# LatencyTester.net
KiCad netlist of a schematic drawn in EAGLE
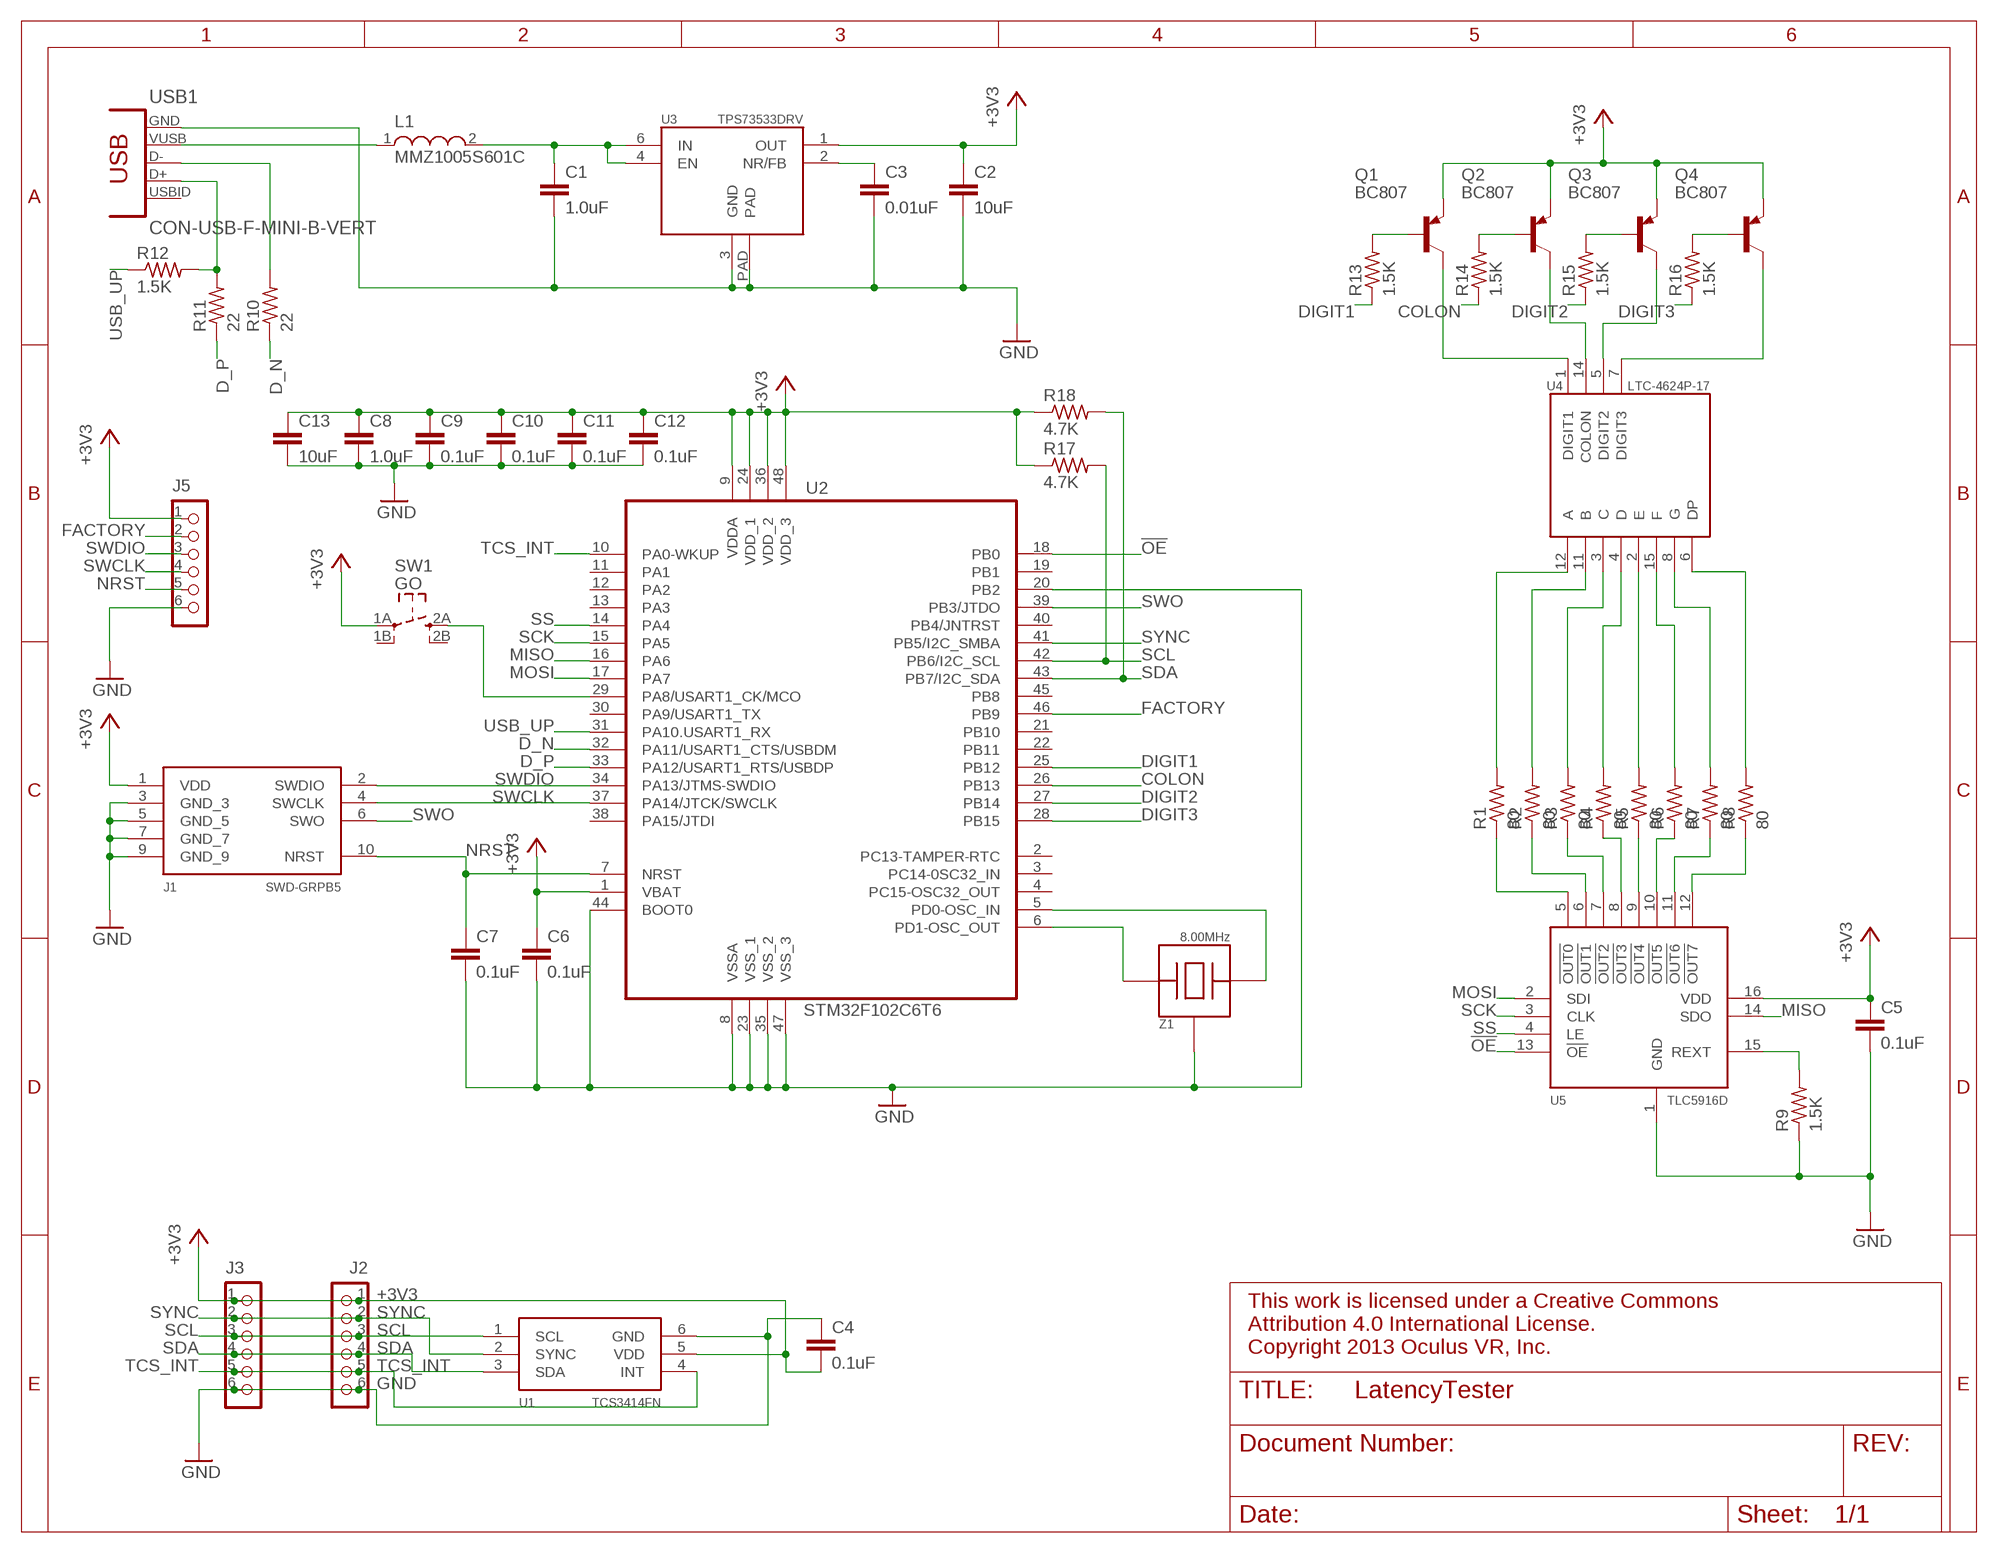
[diagram p0: schematic, sheet 1]

(export (version "E")
  (design (tool "Eeschema 10.0.6"))
  (components
    (comp (ref "C1")
      (value "1.0uF")
      (footprint "eagle-import:C0402")
      (libsource (lib "eagle-import") (part "C-EUC0402"))
    )
    (comp (ref "C2")
      (value "10uF")
      (footprint "eagle-import:C0805")
      (libsource (lib "eagle-import") (part "C-EUC0805"))
    )
    (comp (ref "C3")
      (value "0.01uF")
      (footprint "eagle-import:C0402")
      (libsource (lib "eagle-import") (part "C-EUC0402"))
    )
    (comp (ref "C4")
      (value "0.1uF")
      (footprint "eagle-import:C0402")
      (libsource (lib "eagle-import") (part "C-EUC0402"))
    )
    (comp (ref "C5")
      (value "0.1uF")
      (footprint "eagle-import:C0402")
      (libsource (lib "eagle-import") (part "C-EUC0402"))
    )
    (comp (ref "C6")
      (value "0.1uF")
      (footprint "eagle-import:C0402")
      (libsource (lib "eagle-import") (part "C-EUC0402"))
    )
    (comp (ref "C7")
      (value "0.1uF")
      (footprint "eagle-import:C0402")
      (libsource (lib "eagle-import") (part "C-EUC0402"))
    )
    (comp (ref "C8")
      (value "1.0uF")
      (footprint "eagle-import:C0402")
      (libsource (lib "eagle-import") (part "C-EUC0402"))
    )
    (comp (ref "C9")
      (value "0.1uF")
      (footprint "eagle-import:C0402")
      (libsource (lib "eagle-import") (part "C-EUC0402"))
    )
    (comp (ref "C10")
      (value "0.1uF")
      (footprint "eagle-import:C0402")
      (libsource (lib "eagle-import") (part "C-EUC0402"))
    )
    (comp (ref "C11")
      (value "0.1uF")
      (footprint "eagle-import:C0402")
      (libsource (lib "eagle-import") (part "C-EUC0402"))
    )
    (comp (ref "C12")
      (value "0.1uF")
      (footprint "eagle-import:C0402")
      (libsource (lib "eagle-import") (part "C-EUC0402"))
    )
    (comp (ref "C13")
      (value "10uF")
      (footprint "eagle-import:C0805")
      (libsource (lib "eagle-import") (part "C-EUC0805"))
    )
    (comp (ref "J1")
      (value "SWD-GRPB5")
      (footprint "eagle-import:GRPB5")
      (libsource (lib "eagle-import") (part "SWD-GRPB5"))
    )
    (comp (ref "J2")
      (value "CON_HEADER_1X06-PTH")
      (footprint "eagle-import:M1X6")
      (libsource (lib "eagle-import") (part "CON_HEADER_1X06-PTH"))
    )
    (comp (ref "J3")
      (value "CON_HEADER_1X06-PTH")
      (footprint "eagle-import:M1X6")
      (libsource (lib "eagle-import") (part "CON_HEADER_1X06-PTH"))
    )
    (comp (ref "J5")
      (value "CON_HEADER_1X06-PTH")
      (footprint "eagle-import:M1X6")
      (libsource (lib "eagle-import") (part "CON_HEADER_1X06-PTH"))
    )
    (comp (ref "L1")
      (value "MMZ1005S601C")
      (footprint "eagle-import:C402")
      (libsource (lib "eagle-import") (part "INDUCTOR-L0402"))
    )
    (comp (ref "Q1")
      (value "BC807")
      (footprint "eagle-import:SOT-323")
      (libsource (lib "eagle-import") (part "TRANSISTOR_BJT_PNP-SOT-323"))
    )
    (comp (ref "Q2")
      (value "BC807")
      (footprint "eagle-import:SOT-323")
      (libsource (lib "eagle-import") (part "TRANSISTOR_BJT_PNP-SOT-323"))
    )
    (comp (ref "Q3")
      (value "BC807")
      (footprint "eagle-import:SOT-323")
      (libsource (lib "eagle-import") (part "TRANSISTOR_BJT_PNP-SOT-323"))
    )
    (comp (ref "Q4")
      (value "BC807")
      (footprint "eagle-import:SOT-323")
      (libsource (lib "eagle-import") (part "TRANSISTOR_BJT_PNP-SOT-323"))
    )
    (comp (ref "R1")
      (value "80")
      (footprint "eagle-import:R0402")
      (libsource (lib "eagle-import") (part "R-US_R0402"))
    )
    (comp (ref "R2")
      (value "80")
      (footprint "eagle-import:R0402")
      (libsource (lib "eagle-import") (part "R-US_R0402"))
    )
    (comp (ref "R3")
      (value "80")
      (footprint "eagle-import:R0402")
      (libsource (lib "eagle-import") (part "R-US_R0402"))
    )
    (comp (ref "R4")
      (value "80")
      (footprint "eagle-import:R0402")
      (libsource (lib "eagle-import") (part "R-US_R0402"))
    )
    (comp (ref "R5")
      (value "80")
      (footprint "eagle-import:R0402")
      (libsource (lib "eagle-import") (part "R-US_R0402"))
    )
    (comp (ref "R6")
      (value "80")
      (footprint "eagle-import:R0402")
      (libsource (lib "eagle-import") (part "R-US_R0402"))
    )
    (comp (ref "R7")
      (value "80")
      (footprint "eagle-import:R0402")
      (libsource (lib "eagle-import") (part "R-US_R0402"))
    )
    (comp (ref "R8")
      (value "80")
      (footprint "eagle-import:R0402")
      (libsource (lib "eagle-import") (part "R-US_R0402"))
    )
    (comp (ref "R9")
      (value "1.5K")
      (footprint "eagle-import:R0402")
      (libsource (lib "eagle-import") (part "R-US_R0402"))
    )
    (comp (ref "R10")
      (value "22")
      (footprint "eagle-import:R0402")
      (libsource (lib "eagle-import") (part "R-US_R0402"))
    )
    (comp (ref "R11")
      (value "22")
      (footprint "eagle-import:R0402")
      (libsource (lib "eagle-import") (part "R-US_R0402"))
    )
    (comp (ref "R12")
      (value "1.5K")
      (footprint "eagle-import:R0402")
      (libsource (lib "eagle-import") (part "R-US_R0402"))
    )
    (comp (ref "R13")
      (value "1.5K")
      (footprint "eagle-import:R0402")
      (libsource (lib "eagle-import") (part "R-US_R0402"))
    )
    (comp (ref "R14")
      (value "1.5K")
      (footprint "eagle-import:R0402")
      (libsource (lib "eagle-import") (part "R-US_R0402"))
    )
    (comp (ref "R15")
      (value "1.5K")
      (footprint "eagle-import:R0402")
      (libsource (lib "eagle-import") (part "R-US_R0402"))
    )
    (comp (ref "R16")
      (value "1.5K")
      (footprint "eagle-import:R0402")
      (libsource (lib "eagle-import") (part "R-US_R0402"))
    )
    (comp (ref "R17")
      (value "4.7K")
      (footprint "eagle-import:R0402")
      (libsource (lib "eagle-import") (part "R-US_R0402"))
    )
    (comp (ref "R18")
      (value "4.7K")
      (footprint "eagle-import:R0402")
      (libsource (lib "eagle-import") (part "R-US_R0402"))
    )
    (comp (ref "SW1")
      (value "GO")
      (footprint "eagle-import:ADTS2")
      (libsource (lib "eagle-import") (part "SW_TACT_4P-ADTS2"))
    )
    (comp (ref "U1")
      (value "TCS3414FN")
      (footprint "eagle-import:TCS3414FN")
      (libsource (lib "eagle-import") (part "TCS3414FN"))
    )
    (comp (ref "U2")
      (value "STM32F102C6T6")
      (footprint "eagle-import:LQFP48")
      (libsource (lib "eagle-import") (part "IC_UC_STM32"))
    )
    (comp (ref "U3")
      (value "TPS73533DRV")
      (footprint "eagle-import:SON-6")
      (libsource (lib "eagle-import") (part "TPS735XXDRV"))
    )
    (comp (ref "U4")
      (value "LTC-4624P-17")
      (footprint "eagle-import:LTC-4624")
      (libsource (lib "eagle-import") (part "LTC-4624P-17"))
    )
    (comp (ref "U5")
      (value "TLC5916D")
      (footprint "eagle-import:SOIC-16")
      (libsource (lib "eagle-import") (part "TLC5916D"))
    )
    (comp (ref "USB1")
      (value "CON-USB-F-MINI-B-VERT")
      (footprint "eagle-import:651005136421")
      (libsource (lib "eagle-import") (part "CON-USB-F-MINI-B-VERT"))
    )
    (comp (ref "Z1")
      (value "8.00MHz")
      (footprint "eagle-import:PQRV")
      (libsource (lib "eagle-import") (part "RESONATOR-PQRV-C"))
    )
  )
  (nets
    (net (code "1") (name "+3V3") (class "Default")
      (node (ref "C10") (pin "1") (pinfunction "1_1") (pintype "passive"))
      (node (ref "C11") (pin "1") (pinfunction "1_1") (pintype "passive"))
      (node (ref "C12") (pin "1") (pinfunction "1_1") (pintype "passive"))
      (node (ref "C13") (pin "1") (pinfunction "1_1") (pintype "passive"))
      (node (ref "C2") (pin "1") (pinfunction "1_1") (pintype "passive"))
      (node (ref "C4") (pin "2") (pinfunction "2_2") (pintype "passive"))
      (node (ref "C5") (pin "1") (pinfunction "1_1") (pintype "passive"))
      (node (ref "C6") (pin "1") (pinfunction "1_1") (pintype "passive"))
      (node (ref "C8") (pin "1") (pinfunction "1_1") (pintype "passive"))
      (node (ref "C9") (pin "1") (pinfunction "1_1") (pintype "passive"))
      (node (ref "J1") (pin "1") (pinfunction "VDD_1") (pintype "bidirectional"))
      (node (ref "J2") (pin "1") (pinfunction "1_1") (pintype "bidirectional"))
      (node (ref "J3") (pin "1") (pinfunction "1_1") (pintype "bidirectional"))
      (node (ref "J5") (pin "1") (pinfunction "1_1") (pintype "bidirectional"))
      (node (ref "Q1") (pin "2") (pinfunction "E_2") (pintype "passive"))
      (node (ref "Q2") (pin "2") (pinfunction "E_2") (pintype "passive"))
      (node (ref "Q3") (pin "2") (pinfunction "E_2") (pintype "passive"))
      (node (ref "Q4") (pin "2") (pinfunction "E_2") (pintype "passive"))
      (node (ref "R17") (pin "1") (pinfunction "1_1") (pintype "passive"))
      (node (ref "R18") (pin "1") (pinfunction "1_1") (pintype "passive"))
      (node (ref "SW1") (pin "1A") (pinfunction "1_1A") (pintype "passive"))
      (node (ref "U1") (pin "5") (pinfunction "VDD_5") (pintype "power_in"))
      (node (ref "U2") (pin "1") (pinfunction "VBAT_1") (pintype "bidirectional"))
      (node (ref "U2") (pin "24") (pinfunction "VDD_1_24") (pintype "power_in"))
      (node (ref "U2") (pin "36") (pinfunction "VDD_2_36") (pintype "power_in"))
      (node (ref "U2") (pin "48") (pinfunction "VDD_3_48") (pintype "power_in"))
      (node (ref "U2") (pin "9") (pinfunction "VDDA_9") (pintype "power_in"))
      (node (ref "U3") (pin "1") (pinfunction "OUT_1") (pintype "bidirectional"))
      (node (ref "U5") (pin "16") (pinfunction "VDD_16") (pintype "bidirectional"))
    )
    (net (code "2") (name "/COLON") (class "Default")
      (node (ref "R14") (pin "1") (pinfunction "1_1") (pintype "passive"))
      (node (ref "U2") (pin "26") (pinfunction "PB13_26") (pintype "bidirectional"))
    )
    (net (code "3") (name "/DIGIT1") (class "Default")
      (node (ref "R13") (pin "1") (pinfunction "1_1") (pintype "passive"))
      (node (ref "U2") (pin "25") (pinfunction "PB12_25") (pintype "bidirectional"))
    )
    (net (code "4") (name "/DIGIT2") (class "Default")
      (node (ref "R15") (pin "1") (pinfunction "1_1") (pintype "passive"))
      (node (ref "U2") (pin "27") (pinfunction "PB14_27") (pintype "bidirectional"))
    )
    (net (code "5") (name "/DIGIT3") (class "Default")
      (node (ref "R16") (pin "1") (pinfunction "1_1") (pintype "passive"))
      (node (ref "U2") (pin "28") (pinfunction "PB15_28") (pintype "bidirectional"))
    )
    (net (code "6") (name "/D_N") (class "Default")
      (node (ref "R10") (pin "1") (pinfunction "1_1") (pintype "passive"))
      (node (ref "U2") (pin "32") (pinfunction "PA11/USART1_CTS/USBDM_32") (pintype "bidirectional"))
    )
    (net (code "7") (name "/D_P") (class "Default")
      (node (ref "R11") (pin "1") (pinfunction "1_1") (pintype "passive"))
      (node (ref "U2") (pin "33") (pinfunction "PA12/USART1_RTS/USBDP_33") (pintype "bidirectional"))
    )
    (net (code "8") (name "/FACTORY") (class "Default")
      (node (ref "J5") (pin "2") (pinfunction "2_2") (pintype "bidirectional"))
      (node (ref "U2") (pin "46") (pinfunction "PB9_46") (pintype "bidirectional"))
    )
    (net (code "9") (name "/MISO") (class "Default")
      (node (ref "U2") (pin "16") (pinfunction "PA6_16") (pintype "bidirectional"))
      (node (ref "U5") (pin "14") (pinfunction "SDO_14") (pintype "bidirectional"))
    )
    (net (code "10") (name "/MOSI") (class "Default")
      (node (ref "U2") (pin "17") (pinfunction "PA7_17") (pintype "bidirectional"))
      (node (ref "U5") (pin "2") (pinfunction "SDI_2") (pintype "bidirectional"))
    )
    (net (code "11") (name "/NRST") (class "Default")
      (node (ref "C7") (pin "1") (pinfunction "1_1") (pintype "passive"))
      (node (ref "J1") (pin "10") (pinfunction "NRST_10") (pintype "bidirectional"))
      (node (ref "J5") (pin "5") (pinfunction "5_5") (pintype "passive"))
      (node (ref "U2") (pin "7") (pinfunction "NRST_7") (pintype "bidirectional"))
    )
    (net (code "12") (name "/SCK") (class "Default")
      (node (ref "U2") (pin "15") (pinfunction "PA5_15") (pintype "bidirectional"))
      (node (ref "U5") (pin "3") (pinfunction "CLK_3") (pintype "bidirectional"))
    )
    (net (code "13") (name "/SCL") (class "Default")
      (node (ref "J2") (pin "3") (pinfunction "3_3") (pintype "passive"))
      (node (ref "J3") (pin "3") (pinfunction "3_3") (pintype "passive"))
      (node (ref "R17") (pin "2") (pinfunction "2_2") (pintype "passive"))
      (node (ref "U1") (pin "1") (pinfunction "SCL_1") (pintype "bidirectional"))
      (node (ref "U2") (pin "42") (pinfunction "PB6/I2C_SCL_42") (pintype "bidirectional"))
    )
    (net (code "14") (name "/SDA") (class "Default")
      (node (ref "J2") (pin "4") (pinfunction "4_4") (pintype "passive"))
      (node (ref "J3") (pin "4") (pinfunction "4_4") (pintype "passive"))
      (node (ref "R18") (pin "2") (pinfunction "2_2") (pintype "passive"))
      (node (ref "U1") (pin "3") (pinfunction "SDA_3") (pintype "bidirectional"))
      (node (ref "U2") (pin "43") (pinfunction "PB7/I2C_SDA_43") (pintype "bidirectional"))
    )
    (net (code "15") (name "/SS") (class "Default")
      (node (ref "U2") (pin "14") (pinfunction "PA4_14") (pintype "bidirectional"))
      (node (ref "U5") (pin "4") (pinfunction "LE_4") (pintype "bidirectional"))
    )
    (net (code "16") (name "/SWCLK") (class "Default")
      (node (ref "J1") (pin "4") (pinfunction "SWCLK_4") (pintype "bidirectional"))
      (node (ref "J5") (pin "4") (pinfunction "4_4") (pintype "passive"))
      (node (ref "U2") (pin "37") (pinfunction "PA14/JTCK/SWCLK_37") (pintype "bidirectional"))
    )
    (net (code "17") (name "/SWDIO") (class "Default")
      (node (ref "J1") (pin "2") (pinfunction "SWDIO_2") (pintype "bidirectional"))
      (node (ref "J5") (pin "3") (pinfunction "3_3") (pintype "passive"))
      (node (ref "U2") (pin "34") (pinfunction "PA13/JTMS-SWDIO_34") (pintype "bidirectional"))
    )
    (net (code "18") (name "/SWO") (class "Default")
      (node (ref "J1") (pin "6") (pinfunction "SWO_6") (pintype "bidirectional"))
      (node (ref "U2") (pin "39") (pinfunction "PB3/JTDO_39") (pintype "bidirectional"))
    )
    (net (code "19") (name "/SYNC") (class "Default")
      (node (ref "J2") (pin "2") (pinfunction "2_2") (pintype "bidirectional"))
      (node (ref "J3") (pin "2") (pinfunction "2_2") (pintype "bidirectional"))
      (node (ref "U1") (pin "2") (pinfunction "SYNC_2") (pintype "bidirectional"))
      (node (ref "U2") (pin "41") (pinfunction "PB5/I2C_SMBA_41") (pintype "bidirectional"))
    )
    (net (code "20") (name "/TCS_INT") (class "Default")
      (node (ref "J2") (pin "5") (pinfunction "5_5") (pintype "passive"))
      (node (ref "J3") (pin "5") (pinfunction "5_5") (pintype "passive"))
      (node (ref "U1") (pin "4") (pinfunction "INT_4") (pintype "bidirectional"))
      (node (ref "U2") (pin "10") (pinfunction "PA0-WKUP_10") (pintype "bidirectional"))
    )
    (net (code "21") (name "/USB_UP") (class "Default")
      (node (ref "R12") (pin "1") (pinfunction "1_1") (pintype "passive"))
      (node (ref "U2") (pin "31") (pinfunction "PA10.USART1_RX_31") (pintype "bidirectional"))
    )
    (net (code "22") (name "/~{OE}") (class "Default")
      (node (ref "U2") (pin "18") (pinfunction "PB0_18") (pintype "bidirectional"))
      (node (ref "U5") (pin "13") (pinfunction "~{OE}_13") (pintype "bidirectional"))
    )
    (net (code "23") (name "GND") (class "Default")
      (node (ref "C1") (pin "2") (pinfunction "2_2") (pintype "passive"))
      (node (ref "C10") (pin "2") (pinfunction "2_2") (pintype "passive"))
      (node (ref "C11") (pin "2") (pinfunction "2_2") (pintype "passive"))
      (node (ref "C12") (pin "2") (pinfunction "2_2") (pintype "passive"))
      (node (ref "C13") (pin "2") (pinfunction "2_2") (pintype "passive"))
      (node (ref "C2") (pin "2") (pinfunction "2_2") (pintype "passive"))
      (node (ref "C3") (pin "2") (pinfunction "2_2") (pintype "passive"))
      (node (ref "C4") (pin "1") (pinfunction "1_1") (pintype "passive"))
      (node (ref "C5") (pin "2") (pinfunction "2_2") (pintype "passive"))
      (node (ref "C6") (pin "2") (pinfunction "2_2") (pintype "passive"))
      (node (ref "C7") (pin "2") (pinfunction "2_2") (pintype "passive"))
      (node (ref "C8") (pin "2") (pinfunction "2_2") (pintype "passive"))
      (node (ref "C9") (pin "2") (pinfunction "2_2") (pintype "passive"))
      (node (ref "J1") (pin "3") (pinfunction "GND_3_3") (pintype "bidirectional"))
      (node (ref "J1") (pin "5") (pinfunction "GND_5_5") (pintype "bidirectional"))
      (node (ref "J1") (pin "7") (pinfunction "GND_7_7") (pintype "bidirectional"))
      (node (ref "J1") (pin "9") (pinfunction "GND_9_9") (pintype "bidirectional"))
      (node (ref "J2") (pin "6") (pinfunction "6_6") (pintype "passive"))
      (node (ref "J3") (pin "6") (pinfunction "6_6") (pintype "passive"))
      (node (ref "J5") (pin "6") (pinfunction "6_6") (pintype "passive"))
      (node (ref "R9") (pin "1") (pinfunction "1_1") (pintype "passive"))
      (node (ref "U1") (pin "6") (pinfunction "GND_6") (pintype "power_in"))
      (node (ref "U2") (pin "20") (pinfunction "PB2_20") (pintype "bidirectional"))
      (node (ref "U2") (pin "23") (pinfunction "VSS_1_23") (pintype "power_in"))
      (node (ref "U2") (pin "35") (pinfunction "VSS_2_35") (pintype "power_in"))
      (node (ref "U2") (pin "44") (pinfunction "BOOT0_44") (pintype "bidirectional"))
      (node (ref "U2") (pin "47") (pinfunction "VSS_3_47") (pintype "power_in"))
      (node (ref "U2") (pin "8") (pinfunction "VSSA_8") (pintype "power_in"))
      (node (ref "U3") (pin "3") (pinfunction "GND_3") (pintype "bidirectional"))
      (node (ref "U3") (pin "PAD") (pinfunction "PAD_PAD") (pintype "bidirectional"))
      (node (ref "U5") (pin "1") (pinfunction "GND_1") (pintype "bidirectional"))
      (node (ref "USB1") (pin "5") (pinfunction "GND_5") (pintype "bidirectional"))
      (node (ref "Z1") (pin "2") (pinfunction "GND_2") (pintype "bidirectional"))
    )
    (net (code "24") (name "Net-(Q1-B)") (class "Default")
      (node (ref "Q1") (pin "1") (pinfunction "B_1") (pintype "passive"))
      (node (ref "R13") (pin "2") (pinfunction "2_2") (pintype "passive"))
    )
    (net (code "25") (name "Net-(Q1-C)") (class "Default")
      (node (ref "Q1") (pin "3") (pinfunction "C_3") (pintype "passive"))
      (node (ref "U4") (pin "1") (pinfunction "DIGIT1_1") (pintype "bidirectional"))
    )
    (net (code "26") (name "Net-(Q2-B)") (class "Default")
      (node (ref "Q2") (pin "1") (pinfunction "B_1") (pintype "passive"))
      (node (ref "R14") (pin "2") (pinfunction "2_2") (pintype "passive"))
    )
    (net (code "27") (name "Net-(Q2-C)") (class "Default")
      (node (ref "Q2") (pin "3") (pinfunction "C_3") (pintype "passive"))
      (node (ref "U4") (pin "14") (pinfunction "COLON_14") (pintype "bidirectional"))
    )
    (net (code "28") (name "Net-(Q3-B)") (class "Default")
      (node (ref "Q3") (pin "1") (pinfunction "B_1") (pintype "passive"))
      (node (ref "R15") (pin "2") (pinfunction "2_2") (pintype "passive"))
    )
    (net (code "29") (name "Net-(Q3-C)") (class "Default")
      (node (ref "Q3") (pin "3") (pinfunction "C_3") (pintype "passive"))
      (node (ref "U4") (pin "5") (pinfunction "DIGIT2_5") (pintype "bidirectional"))
    )
    (net (code "30") (name "Net-(Q4-B)") (class "Default")
      (node (ref "Q4") (pin "1") (pinfunction "B_1") (pintype "passive"))
      (node (ref "R16") (pin "2") (pinfunction "2_2") (pintype "passive"))
    )
    (net (code "31") (name "Net-(Q4-C)") (class "Default")
      (node (ref "Q4") (pin "3") (pinfunction "C_3") (pintype "passive"))
      (node (ref "U4") (pin "7") (pinfunction "DIGIT3_7") (pintype "bidirectional"))
    )
    (net (code "32") (name "Net-(SW1-3)") (class "Default")
      (node (ref "SW1") (pin "2A") (pinfunction "3_2A") (pintype "passive"))
      (node (ref "U2") (pin "29") (pinfunction "PA8/USART1_CK/MCO_29") (pintype "bidirectional"))
    )
    (net (code "33") (name "Net-(U2-PD0-OSC_IN)") (class "Default")
      (node (ref "U2") (pin "5") (pinfunction "PD0-OSC_IN_5") (pintype "bidirectional"))
      (node (ref "Z1") (pin "3") (pinfunction "OUT_3") (pintype "bidirectional"))
    )
    (net (code "34") (name "Net-(U2-PD1-OSC_OUT)") (class "Default")
      (node (ref "U2") (pin "6") (pinfunction "PD1-OSC_OUT_6") (pintype "bidirectional"))
      (node (ref "Z1") (pin "1") (pinfunction "IN_1") (pintype "bidirectional"))
    )
    (net (code "35") (name "Net-(U3-EN)") (class "Default")
      (node (ref "C1") (pin "1") (pinfunction "1_1") (pintype "passive"))
      (node (ref "L1") (pin "2") (pinfunction "2_2") (pintype "passive"))
      (node (ref "U3") (pin "4") (pinfunction "EN_4") (pintype "bidirectional"))
      (node (ref "U3") (pin "6") (pinfunction "IN_6") (pintype "bidirectional"))
    )
    (net (code "36") (name "Net-(U3-NR{slash}FB)") (class "Default")
      (node (ref "C3") (pin "1") (pinfunction "1_1") (pintype "passive"))
      (node (ref "U3") (pin "2") (pinfunction "NR/FB_2") (pintype "bidirectional"))
    )
    (net (code "37") (name "Net-(U4-A)") (class "Default")
      (node (ref "R1") (pin "2") (pinfunction "2_2") (pintype "passive"))
      (node (ref "U4") (pin "12") (pinfunction "A_12") (pintype "bidirectional"))
    )
    (net (code "38") (name "Net-(U4-B)") (class "Default")
      (node (ref "R2") (pin "2") (pinfunction "2_2") (pintype "passive"))
      (node (ref "U4") (pin "11") (pinfunction "B_11") (pintype "bidirectional"))
    )
    (net (code "39") (name "Net-(U4-C)") (class "Default")
      (node (ref "R3") (pin "2") (pinfunction "2_2") (pintype "passive"))
      (node (ref "U4") (pin "3") (pinfunction "C_3") (pintype "bidirectional"))
    )
    (net (code "40") (name "Net-(U4-D)") (class "Default")
      (node (ref "R4") (pin "2") (pinfunction "2_2") (pintype "passive"))
      (node (ref "U4") (pin "4") (pinfunction "D_4") (pintype "bidirectional"))
    )
    (net (code "41") (name "Net-(U4-DP)") (class "Default")
      (node (ref "R8") (pin "2") (pinfunction "2_2") (pintype "passive"))
      (node (ref "U4") (pin "6") (pinfunction "DP_6") (pintype "bidirectional"))
    )
    (net (code "42") (name "Net-(U4-E)") (class "Default")
      (node (ref "R5") (pin "2") (pinfunction "2_2") (pintype "passive"))
      (node (ref "U4") (pin "2") (pinfunction "E_2") (pintype "bidirectional"))
    )
    (net (code "43") (name "Net-(U4-F)") (class "Default")
      (node (ref "R6") (pin "2") (pinfunction "2_2") (pintype "passive"))
      (node (ref "U4") (pin "15") (pinfunction "F_15") (pintype "bidirectional"))
    )
    (net (code "44") (name "Net-(U4-G)") (class "Default")
      (node (ref "R7") (pin "2") (pinfunction "2_2") (pintype "passive"))
      (node (ref "U4") (pin "8") (pinfunction "G_8") (pintype "bidirectional"))
    )
    (net (code "45") (name "Net-(U5-REXT)") (class "Default")
      (node (ref "R9") (pin "2") (pinfunction "2_2") (pintype "passive"))
      (node (ref "U5") (pin "15") (pinfunction "REXT_15") (pintype "bidirectional"))
    )
    (net (code "46") (name "Net-(U5-~{OUT0})") (class "Default")
      (node (ref "R1") (pin "1") (pinfunction "1_1") (pintype "passive"))
      (node (ref "U5") (pin "5") (pinfunction "~{OUT0}_5") (pintype "bidirectional"))
    )
    (net (code "47") (name "Net-(U5-~{OUT1})") (class "Default")
      (node (ref "R2") (pin "1") (pinfunction "1_1") (pintype "passive"))
      (node (ref "U5") (pin "6") (pinfunction "~{OUT1}_6") (pintype "bidirectional"))
    )
    (net (code "48") (name "Net-(U5-~{OUT2})") (class "Default")
      (node (ref "R3") (pin "1") (pinfunction "1_1") (pintype "passive"))
      (node (ref "U5") (pin "7") (pinfunction "~{OUT2}_7") (pintype "bidirectional"))
    )
    (net (code "49") (name "Net-(U5-~{OUT3})") (class "Default")
      (node (ref "R4") (pin "1") (pinfunction "1_1") (pintype "passive"))
      (node (ref "U5") (pin "8") (pinfunction "~{OUT3}_8") (pintype "bidirectional"))
    )
    (net (code "50") (name "Net-(U5-~{OUT4})") (class "Default")
      (node (ref "R5") (pin "1") (pinfunction "1_1") (pintype "passive"))
      (node (ref "U5") (pin "9") (pinfunction "~{OUT4}_9") (pintype "bidirectional"))
    )
    (net (code "51") (name "Net-(U5-~{OUT5})") (class "Default")
      (node (ref "R6") (pin "1") (pinfunction "1_1") (pintype "passive"))
      (node (ref "U5") (pin "10") (pinfunction "~{OUT5}_10") (pintype "bidirectional"))
    )
    (net (code "52") (name "Net-(U5-~{OUT6})") (class "Default")
      (node (ref "R7") (pin "1") (pinfunction "1_1") (pintype "passive"))
      (node (ref "U5") (pin "11") (pinfunction "~{OUT6}_11") (pintype "bidirectional"))
    )
    (net (code "53") (name "Net-(U5-~{OUT7})") (class "Default")
      (node (ref "R8") (pin "1") (pinfunction "1_1") (pintype "passive"))
      (node (ref "U5") (pin "12") (pinfunction "~{OUT7}_12") (pintype "bidirectional"))
    )
    (net (code "54") (name "Net-(USB1-D+)") (class "Default")
      (node (ref "R11") (pin "2") (pinfunction "2_2") (pintype "passive"))
      (node (ref "R12") (pin "2") (pinfunction "2_2") (pintype "passive"))
      (node (ref "USB1") (pin "3") (pinfunction "D+_3") (pintype "bidirectional"))
    )
    (net (code "55") (name "Net-(USB1-D-)") (class "Default")
      (node (ref "R10") (pin "2") (pinfunction "2_2") (pintype "passive"))
      (node (ref "USB1") (pin "2") (pinfunction "D-_2") (pintype "bidirectional"))
    )
    (net (code "56") (name "Net-(USB1-VUSB)") (class "Default")
      (node (ref "L1") (pin "1") (pinfunction "1_1") (pintype "passive"))
      (node (ref "USB1") (pin "1") (pinfunction "VUSB_1") (pintype "bidirectional"))
    )
    (net (code "57") (name "unconnected-(SW1-2-Pad1B)") (class "Default")
      (node (ref "SW1") (pin "1B") (pinfunction "2_1B") (pintype "passive"))
    )
    (net (code "58") (name "unconnected-(SW1-4-Pad2B)") (class "Default")
      (node (ref "SW1") (pin "2B") (pinfunction "4_2B") (pintype "passive"))
    )
    (net (code "59") (name "unconnected-(U2-PA1-Pad11)") (class "Default")
      (node (ref "U2") (pin "11") (pinfunction "PA1_11") (pintype "bidirectional"))
    )
    (net (code "60") (name "unconnected-(U2-PA2-Pad12)") (class "Default")
      (node (ref "U2") (pin "12") (pinfunction "PA2_12") (pintype "bidirectional"))
    )
    (net (code "61") (name "unconnected-(U2-PA3-Pad13)") (class "Default")
      (node (ref "U2") (pin "13") (pinfunction "PA3_13") (pintype "bidirectional"))
    )
    (net (code "62") (name "unconnected-(U2-PA9{slash}USART1_TX-Pad30)") (class "Default")
      (node (ref "U2") (pin "30") (pinfunction "PA9/USART1_TX_30") (pintype "bidirectional"))
    )
    (net (code "63") (name "unconnected-(U2-PA15{slash}JTDI-Pad38)") (class "Default")
      (node (ref "U2") (pin "38") (pinfunction "PA15/JTDI_38") (pintype "bidirectional"))
    )
    (net (code "64") (name "unconnected-(U2-PB1-Pad19)") (class "Default")
      (node (ref "U2") (pin "19") (pinfunction "PB1_19") (pintype "bidirectional"))
    )
    (net (code "65") (name "unconnected-(U2-PB4{slash}JNTRST-Pad40)") (class "Default")
      (node (ref "U2") (pin "40") (pinfunction "PB4/JNTRST_40") (pintype "bidirectional"))
    )
    (net (code "66") (name "unconnected-(U2-PB8-Pad45)") (class "Default")
      (node (ref "U2") (pin "45") (pinfunction "PB8_45") (pintype "bidirectional"))
    )
    (net (code "67") (name "unconnected-(U2-PB10-Pad21)") (class "Default")
      (node (ref "U2") (pin "21") (pinfunction "PB10_21") (pintype "bidirectional"))
    )
    (net (code "68") (name "unconnected-(U2-PB11-Pad22)") (class "Default")
      (node (ref "U2") (pin "22") (pinfunction "PB11_22") (pintype "bidirectional"))
    )
    (net (code "69") (name "unconnected-(U2-PC13-TAMPER-RTC-Pad2)") (class "Default")
      (node (ref "U2") (pin "2") (pinfunction "PC13-TAMPER-RTC_2") (pintype "bidirectional"))
    )
    (net (code "70") (name "unconnected-(U2-PC14-0SC32_IN-Pad3)") (class "Default")
      (node (ref "U2") (pin "3") (pinfunction "PC14-0SC32_IN_3") (pintype "bidirectional"))
    )
    (net (code "71") (name "unconnected-(U2-PC15-OSC32_OUT-Pad4)") (class "Default")
      (node (ref "U2") (pin "4") (pinfunction "PC15-OSC32_OUT_4") (pintype "bidirectional"))
    )
    (net (code "72") (name "unconnected-(USB1-USBID-Pad4)") (class "Default")
      (node (ref "USB1") (pin "4") (pinfunction "USBID_4") (pintype "bidirectional"))
    )
  )
)
